# TD4-CORE.net
KiCad netlist of a schematic drawn in Altium Designer
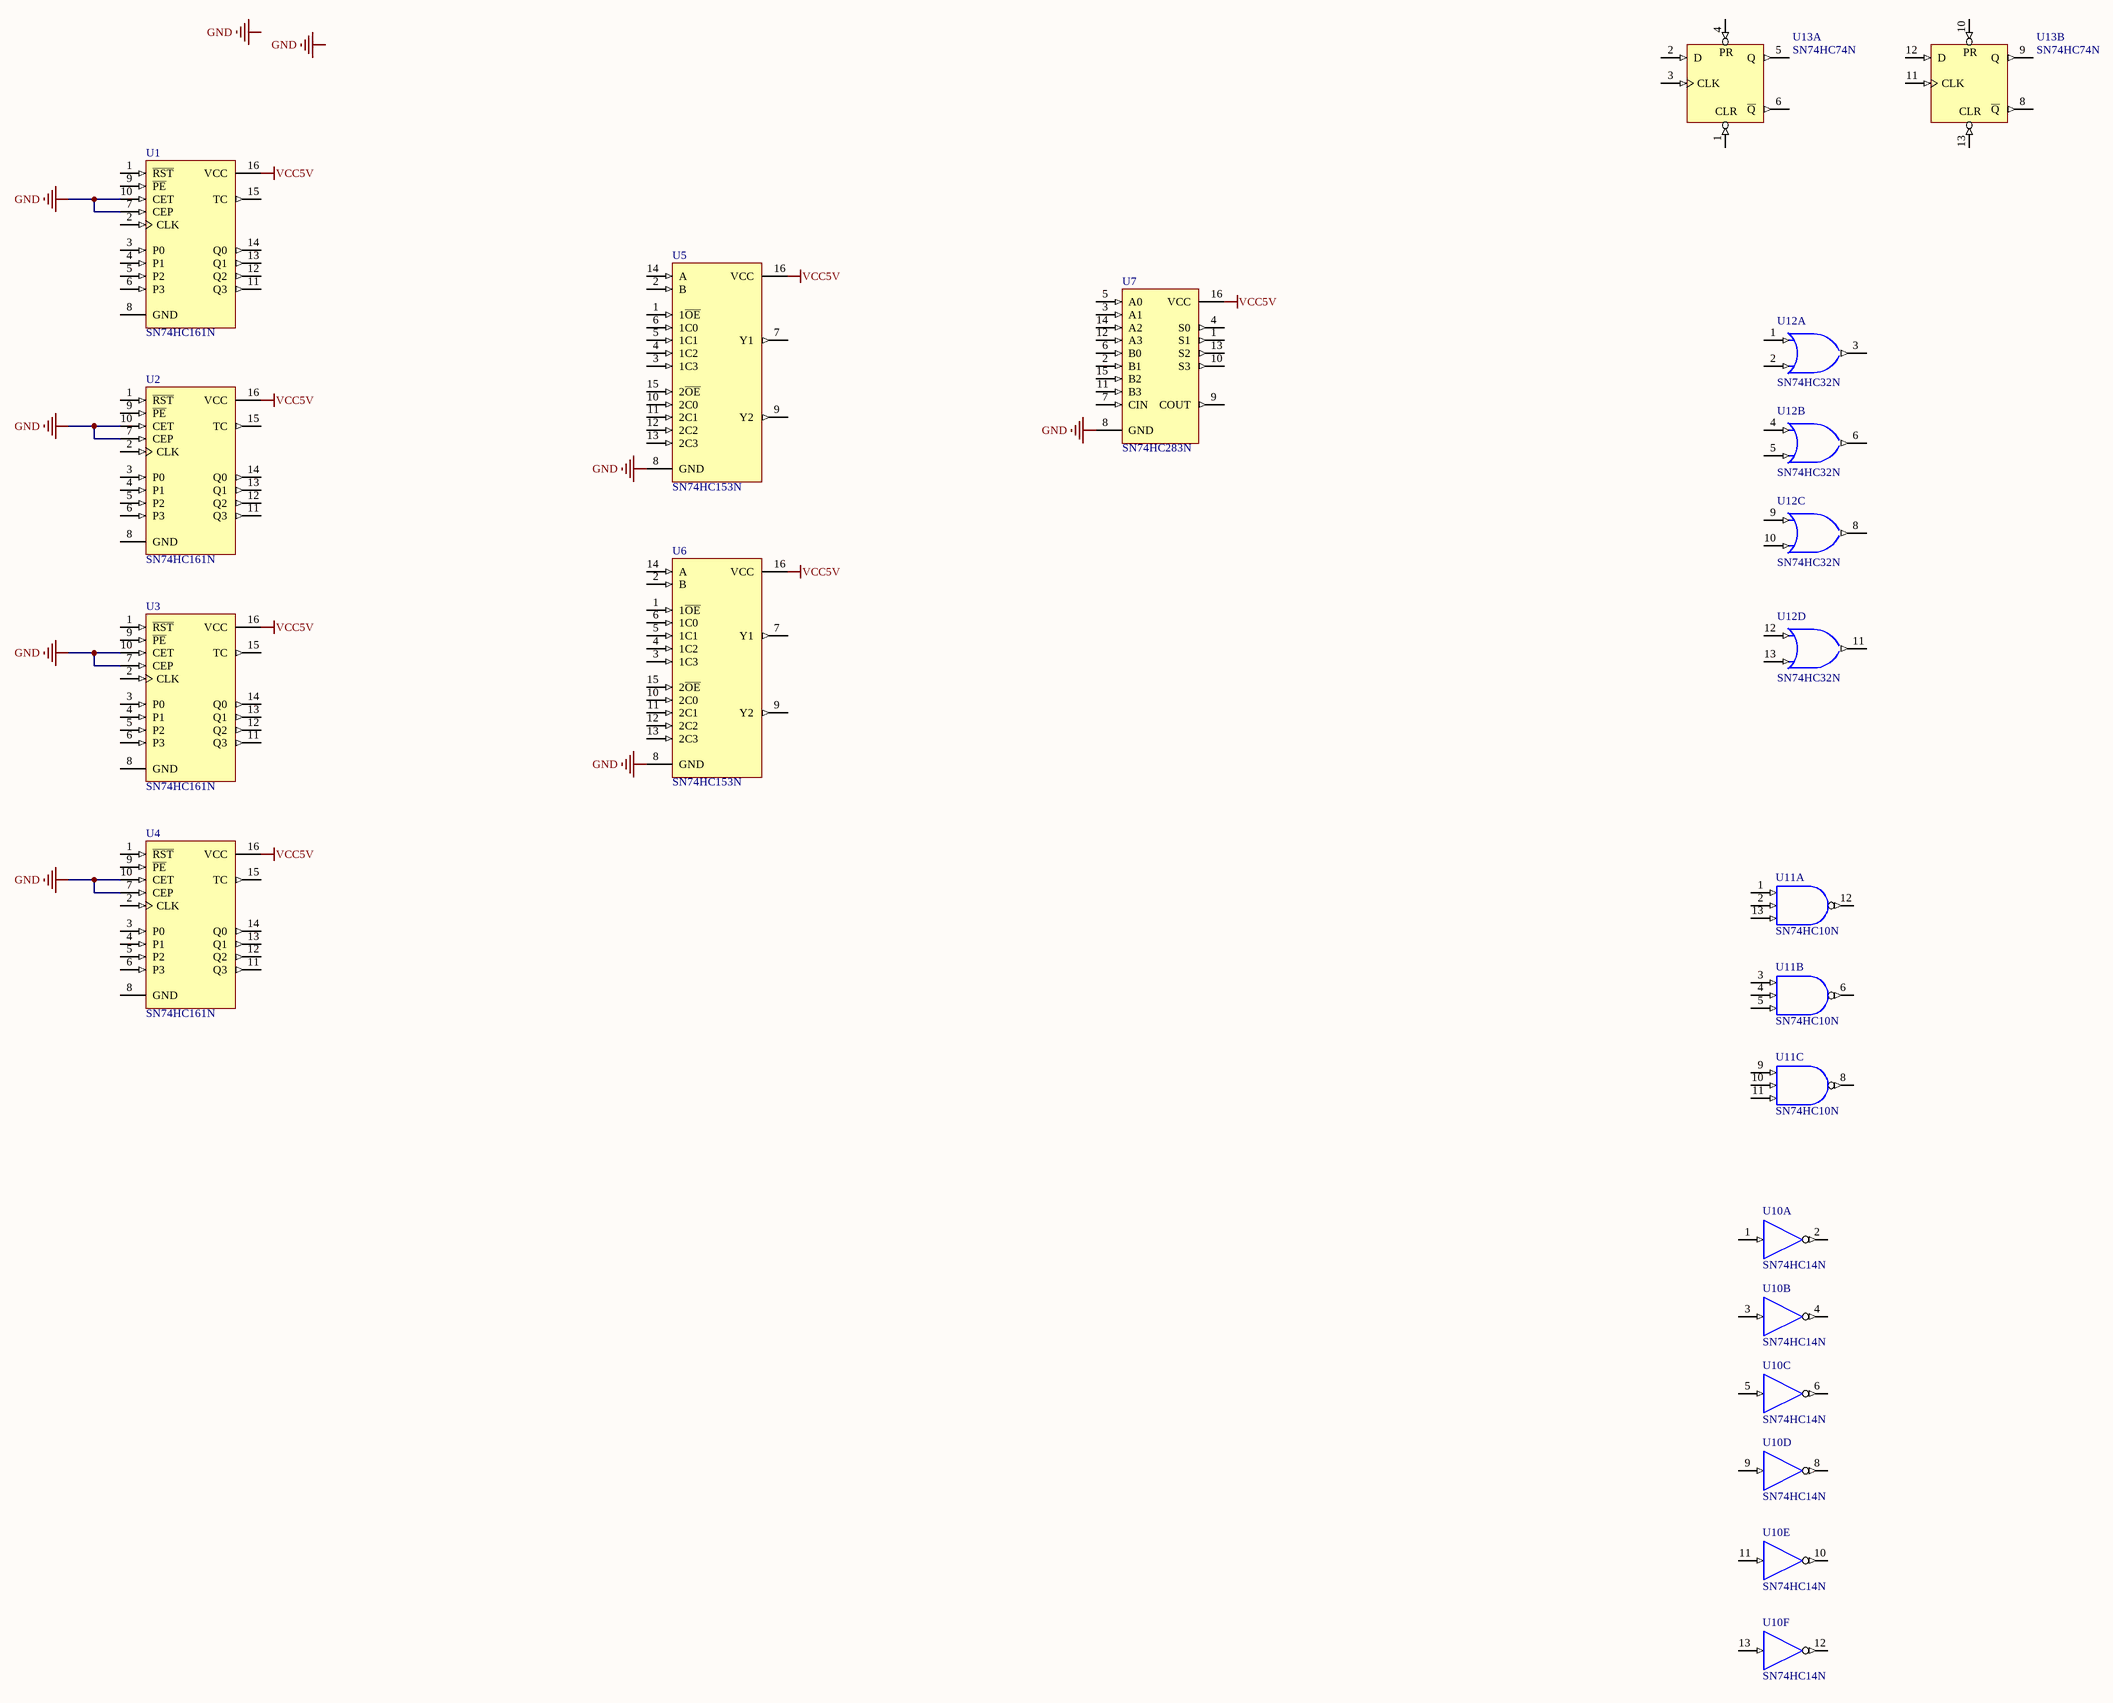
[diagram p0: TD4-CORE.SchDoc]

(export (version "E")
  (design (tool "Eeschema 10.0.6"))
  (components
    (comp (ref "U1")
      (value "SN74HC161N")
      (footprint "N016")
      (description "4-Bit Synchronous Binary Counter")
      (fields (field (name "PUBLISHER") "Altium Limited"))
      (libsource (lib "TI Logic Counter") (part "SN74HC161N"))
    )
    (comp (ref "U2")
      (value "SN74HC161N")
      (footprint "N016")
      (description "4-Bit Synchronous Binary Counter")
      (fields (field (name "PUBLISHER") "Altium Limited"))
      (libsource (lib "TI Logic Counter") (part "SN74HC161N"))
    )
    (comp (ref "U3")
      (value "SN74HC161N")
      (footprint "N016")
      (description "4-Bit Synchronous Binary Counter")
      (fields (field (name "PUBLISHER") "Altium Limited"))
      (libsource (lib "TI Logic Counter") (part "SN74HC161N"))
    )
    (comp (ref "U4")
      (value "SN74HC161N")
      (footprint "N016")
      (description "4-Bit Synchronous Binary Counter")
      (fields (field (name "PUBLISHER") "Altium Limited"))
      (libsource (lib "TI Logic Counter") (part "SN74HC161N"))
    )
    (comp (ref "U5")
      (value "SN74HC153N")
      (footprint "N016")
      (description "Dual 4-Line to 1-Line Data Selector/Multiplexer")
      (fields (field (name "PUBLISHER") "Altium Limited"))
      (libsource (lib "TI Logic Multiplexer") (part "SN74HC153N"))
    )
    (comp (ref "U6")
      (value "SN74HC153N")
      (footprint "N016")
      (description "Dual 4-Line to 1-Line Data Selector/Multiplexer")
      (fields (field (name "PUBLISHER") "Altium Limited"))
      (libsource (lib "TI Logic Multiplexer") (part "SN74HC153N"))
    )
    (comp (ref "U7")
      (value "SN74HC283N")
      (footprint "N016")
      (description "4-Bit Binary Full Adder with Fast Carry")
      (fields (field (name "PUBLISHER") "Altium Limited"))
      (libsource (lib "TI Logic Arithmetic") (part "SN74HC283N"))
    )
    (comp (ref "U10")
      (value "SN74HC14N")
      (footprint "N014")
      (description "Hex Schmitt-Trigger Inverter")
      (fields (field (name "PUBLISHER") "Altium Limited"))
      (libsource (lib "TI Logic Gate 2") (part "SN74HC14N"))
    )
    (comp (ref "U11")
      (value "SN74HC10N")
      (footprint "N014")
      (description "Triple 3-Input Positive-NAND Gate")
      (fields (field (name "PUBLISHER") "Altium Limited"))
      (libsource (lib "TI Logic Gate 2") (part "SN74HC10N"))
    )
    (comp (ref "U12")
      (value "SN74HC32N")
      (footprint "N014")
      (description "Quadruple 2-Input Positive-OR Gate")
      (fields (field (name "PUBLISHER") "Altium Limited"))
      (libsource (lib "TI Logic Gate 2") (part "SN74HC32N"))
    )
    (comp (ref "U13")
      (value "SN74HC74N")
      (footprint "N014")
      (description "Dual D-Type Positive-Edge-Triggered Flip-Flop with Clear and Preset")
      (fields (field (name "PUBLISHER") "Altium Limited"))
      (libsource (lib "TI Logic Flip-Flop") (part "SN74HC74N"))
    )
  )
  (nets
    (net (code "1") (name "GND") (class "Default")
      (node (ref "U1") (pin "10") (pinfunction "CET_10") (pintype "input"))
      (node (ref "U1") (pin "7") (pinfunction "CEP_7") (pintype "input"))
      (node (ref "U10") (pin "7") (pinfunction "GND_7") (pintype "power_in"))
      (node (ref "U11") (pin "7") (pinfunction "GND_7") (pintype "power_in"))
      (node (ref "U12") (pin "7") (pinfunction "GND_7") (pintype "power_in"))
      (node (ref "U13") (pin "7") (pinfunction "GND_7") (pintype "power_in"))
      (node (ref "U2") (pin "10") (pinfunction "CET_10") (pintype "input"))
      (node (ref "U2") (pin "7") (pinfunction "CEP_7") (pintype "input"))
      (node (ref "U3") (pin "10") (pinfunction "CET_10") (pintype "input"))
      (node (ref "U3") (pin "7") (pinfunction "CEP_7") (pintype "input"))
      (node (ref "U4") (pin "10") (pinfunction "CET_10") (pintype "input"))
      (node (ref "U4") (pin "7") (pinfunction "CEP_7") (pintype "input"))
      (node (ref "U5") (pin "8") (pinfunction "GND_8") (pintype "power_in"))
      (node (ref "U6") (pin "8") (pinfunction "GND_8") (pintype "power_in"))
      (node (ref "U7") (pin "8") (pinfunction "GND_8") (pintype "power_in"))
    )
    (net (code "2") (name "VCC") (class "Default")
      (node (ref "U10") (pin "14") (pinfunction "VCC_14") (pintype "power_in"))
      (node (ref "U11") (pin "14") (pinfunction "VCC_14") (pintype "power_in"))
      (node (ref "U12") (pin "14") (pinfunction "VCC_14") (pintype "power_in"))
      (node (ref "U13") (pin "14") (pinfunction "VCC_14") (pintype "power_in"))
    )
    (net (code "3") (name "VCC5V") (class "Default")
      (node (ref "U1") (pin "16") (pinfunction "VCC_16") (pintype "power_in"))
      (node (ref "U2") (pin "16") (pinfunction "VCC_16") (pintype "power_in"))
      (node (ref "U3") (pin "16") (pinfunction "VCC_16") (pintype "power_in"))
      (node (ref "U4") (pin "16") (pinfunction "VCC_16") (pintype "power_in"))
      (node (ref "U5") (pin "16") (pinfunction "VCC_16") (pintype "power_in"))
      (node (ref "U6") (pin "16") (pinfunction "VCC_16") (pintype "power_in"))
      (node (ref "U7") (pin "16") (pinfunction "VCC_16") (pintype "power_in"))
    )
    (net (code "4") (name "unconnected-(U1-CLK-Pad2)") (class "Default")
      (node (ref "U1") (pin "2") (pinfunction "CLK_2") (pintype "input"))
    )
    (net (code "5") (name "unconnected-(U1-GND-Pad8)") (class "Default")
      (node (ref "U1") (pin "8") (pinfunction "GND_8") (pintype "power_in"))
    )
    (net (code "6") (name "unconnected-(U1-P0-Pad3)") (class "Default")
      (node (ref "U1") (pin "3") (pinfunction "P0_3") (pintype "input"))
    )
    (net (code "7") (name "unconnected-(U1-P1-Pad4)") (class "Default")
      (node (ref "U1") (pin "4") (pinfunction "P1_4") (pintype "input"))
    )
    (net (code "8") (name "unconnected-(U1-P2-Pad5)") (class "Default")
      (node (ref "U1") (pin "5") (pinfunction "P2_5") (pintype "input"))
    )
    (net (code "9") (name "unconnected-(U1-P3-Pad6)") (class "Default")
      (node (ref "U1") (pin "6") (pinfunction "P3_6") (pintype "input"))
    )
    (net (code "10") (name "unconnected-(U1-Q0-Pad14)") (class "Default")
      (node (ref "U1") (pin "14") (pinfunction "Q0_14") (pintype "output"))
    )
    (net (code "11") (name "unconnected-(U1-Q1-Pad13)") (class "Default")
      (node (ref "U1") (pin "13") (pinfunction "Q1_13") (pintype "output"))
    )
    (net (code "12") (name "unconnected-(U1-Q2-Pad12)") (class "Default")
      (node (ref "U1") (pin "12") (pinfunction "Q2_12") (pintype "output"))
    )
    (net (code "13") (name "unconnected-(U1-Q3-Pad11)") (class "Default")
      (node (ref "U1") (pin "11") (pinfunction "Q3_11") (pintype "output"))
    )
    (net (code "14") (name "unconnected-(U1-TC-Pad15)") (class "Default")
      (node (ref "U1") (pin "15") (pinfunction "TC_15") (pintype "output"))
    )
    (net (code "15") (name "unconnected-(U1-~{PE}-Pad9)") (class "Default")
      (node (ref "U1") (pin "9") (pinfunction "~{PE}_9") (pintype "input"))
    )
    (net (code "16") (name "unconnected-(U1-~{RST}-Pad1)") (class "Default")
      (node (ref "U1") (pin "1") (pinfunction "~{RST}_1") (pintype "input"))
    )
    (net (code "17") (name "unconnected-(U2-CLK-Pad2)") (class "Default")
      (node (ref "U2") (pin "2") (pinfunction "CLK_2") (pintype "input"))
    )
    (net (code "18") (name "unconnected-(U2-GND-Pad8)") (class "Default")
      (node (ref "U2") (pin "8") (pinfunction "GND_8") (pintype "power_in"))
    )
    (net (code "19") (name "unconnected-(U2-P0-Pad3)") (class "Default")
      (node (ref "U2") (pin "3") (pinfunction "P0_3") (pintype "input"))
    )
    (net (code "20") (name "unconnected-(U2-P1-Pad4)") (class "Default")
      (node (ref "U2") (pin "4") (pinfunction "P1_4") (pintype "input"))
    )
    (net (code "21") (name "unconnected-(U2-P2-Pad5)") (class "Default")
      (node (ref "U2") (pin "5") (pinfunction "P2_5") (pintype "input"))
    )
    (net (code "22") (name "unconnected-(U2-P3-Pad6)") (class "Default")
      (node (ref "U2") (pin "6") (pinfunction "P3_6") (pintype "input"))
    )
    (net (code "23") (name "unconnected-(U2-Q0-Pad14)") (class "Default")
      (node (ref "U2") (pin "14") (pinfunction "Q0_14") (pintype "output"))
    )
    (net (code "24") (name "unconnected-(U2-Q1-Pad13)") (class "Default")
      (node (ref "U2") (pin "13") (pinfunction "Q1_13") (pintype "output"))
    )
    (net (code "25") (name "unconnected-(U2-Q2-Pad12)") (class "Default")
      (node (ref "U2") (pin "12") (pinfunction "Q2_12") (pintype "output"))
    )
    (net (code "26") (name "unconnected-(U2-Q3-Pad11)") (class "Default")
      (node (ref "U2") (pin "11") (pinfunction "Q3_11") (pintype "output"))
    )
    (net (code "27") (name "unconnected-(U2-TC-Pad15)") (class "Default")
      (node (ref "U2") (pin "15") (pinfunction "TC_15") (pintype "output"))
    )
    (net (code "28") (name "unconnected-(U2-~{PE}-Pad9)") (class "Default")
      (node (ref "U2") (pin "9") (pinfunction "~{PE}_9") (pintype "input"))
    )
    (net (code "29") (name "unconnected-(U2-~{RST}-Pad1)") (class "Default")
      (node (ref "U2") (pin "1") (pinfunction "~{RST}_1") (pintype "input"))
    )
    (net (code "30") (name "unconnected-(U3-CLK-Pad2)") (class "Default")
      (node (ref "U3") (pin "2") (pinfunction "CLK_2") (pintype "input"))
    )
    (net (code "31") (name "unconnected-(U3-GND-Pad8)") (class "Default")
      (node (ref "U3") (pin "8") (pinfunction "GND_8") (pintype "power_in"))
    )
    (net (code "32") (name "unconnected-(U3-P0-Pad3)") (class "Default")
      (node (ref "U3") (pin "3") (pinfunction "P0_3") (pintype "input"))
    )
    (net (code "33") (name "unconnected-(U3-P1-Pad4)") (class "Default")
      (node (ref "U3") (pin "4") (pinfunction "P1_4") (pintype "input"))
    )
    (net (code "34") (name "unconnected-(U3-P2-Pad5)") (class "Default")
      (node (ref "U3") (pin "5") (pinfunction "P2_5") (pintype "input"))
    )
    (net (code "35") (name "unconnected-(U3-P3-Pad6)") (class "Default")
      (node (ref "U3") (pin "6") (pinfunction "P3_6") (pintype "input"))
    )
    (net (code "36") (name "unconnected-(U3-Q0-Pad14)") (class "Default")
      (node (ref "U3") (pin "14") (pinfunction "Q0_14") (pintype "output"))
    )
    (net (code "37") (name "unconnected-(U3-Q1-Pad13)") (class "Default")
      (node (ref "U3") (pin "13") (pinfunction "Q1_13") (pintype "output"))
    )
    (net (code "38") (name "unconnected-(U3-Q2-Pad12)") (class "Default")
      (node (ref "U3") (pin "12") (pinfunction "Q2_12") (pintype "output"))
    )
    (net (code "39") (name "unconnected-(U3-Q3-Pad11)") (class "Default")
      (node (ref "U3") (pin "11") (pinfunction "Q3_11") (pintype "output"))
    )
    (net (code "40") (name "unconnected-(U3-TC-Pad15)") (class "Default")
      (node (ref "U3") (pin "15") (pinfunction "TC_15") (pintype "output"))
    )
    (net (code "41") (name "unconnected-(U3-~{PE}-Pad9)") (class "Default")
      (node (ref "U3") (pin "9") (pinfunction "~{PE}_9") (pintype "input"))
    )
    (net (code "42") (name "unconnected-(U3-~{RST}-Pad1)") (class "Default")
      (node (ref "U3") (pin "1") (pinfunction "~{RST}_1") (pintype "input"))
    )
    (net (code "43") (name "unconnected-(U4-CLK-Pad2)") (class "Default")
      (node (ref "U4") (pin "2") (pinfunction "CLK_2") (pintype "input"))
    )
    (net (code "44") (name "unconnected-(U4-GND-Pad8)") (class "Default")
      (node (ref "U4") (pin "8") (pinfunction "GND_8") (pintype "power_in"))
    )
    (net (code "45") (name "unconnected-(U4-P0-Pad3)") (class "Default")
      (node (ref "U4") (pin "3") (pinfunction "P0_3") (pintype "input"))
    )
    (net (code "46") (name "unconnected-(U4-P1-Pad4)") (class "Default")
      (node (ref "U4") (pin "4") (pinfunction "P1_4") (pintype "input"))
    )
    (net (code "47") (name "unconnected-(U4-P2-Pad5)") (class "Default")
      (node (ref "U4") (pin "5") (pinfunction "P2_5") (pintype "input"))
    )
    (net (code "48") (name "unconnected-(U4-P3-Pad6)") (class "Default")
      (node (ref "U4") (pin "6") (pinfunction "P3_6") (pintype "input"))
    )
    (net (code "49") (name "unconnected-(U4-Q0-Pad14)") (class "Default")
      (node (ref "U4") (pin "14") (pinfunction "Q0_14") (pintype "output"))
    )
    (net (code "50") (name "unconnected-(U4-Q1-Pad13)") (class "Default")
      (node (ref "U4") (pin "13") (pinfunction "Q1_13") (pintype "output"))
    )
    (net (code "51") (name "unconnected-(U4-Q2-Pad12)") (class "Default")
      (node (ref "U4") (pin "12") (pinfunction "Q2_12") (pintype "output"))
    )
    (net (code "52") (name "unconnected-(U4-Q3-Pad11)") (class "Default")
      (node (ref "U4") (pin "11") (pinfunction "Q3_11") (pintype "output"))
    )
    (net (code "53") (name "unconnected-(U4-TC-Pad15)") (class "Default")
      (node (ref "U4") (pin "15") (pinfunction "TC_15") (pintype "output"))
    )
    (net (code "54") (name "unconnected-(U4-~{PE}-Pad9)") (class "Default")
      (node (ref "U4") (pin "9") (pinfunction "~{PE}_9") (pintype "input"))
    )
    (net (code "55") (name "unconnected-(U4-~{RST}-Pad1)") (class "Default")
      (node (ref "U4") (pin "1") (pinfunction "~{RST}_1") (pintype "input"))
    )
    (net (code "56") (name "unconnected-(U5-1C0-Pad6)") (class "Default")
      (node (ref "U5") (pin "6") (pinfunction "1C0_6") (pintype "input"))
    )
    (net (code "57") (name "unconnected-(U5-1C1-Pad5)") (class "Default")
      (node (ref "U5") (pin "5") (pinfunction "1C1_5") (pintype "input"))
    )
    (net (code "58") (name "unconnected-(U5-1C2-Pad4)") (class "Default")
      (node (ref "U5") (pin "4") (pinfunction "1C2_4") (pintype "input"))
    )
    (net (code "59") (name "unconnected-(U5-1C3-Pad3)") (class "Default")
      (node (ref "U5") (pin "3") (pinfunction "1C3_3") (pintype "input"))
    )
    (net (code "60") (name "unconnected-(U5-1~{OE}-Pad1)") (class "Default")
      (node (ref "U5") (pin "1") (pinfunction "1~{OE}_1") (pintype "input"))
    )
    (net (code "61") (name "unconnected-(U5-2C0-Pad10)") (class "Default")
      (node (ref "U5") (pin "10") (pinfunction "2C0_10") (pintype "input"))
    )
    (net (code "62") (name "unconnected-(U5-2C1-Pad11)") (class "Default")
      (node (ref "U5") (pin "11") (pinfunction "2C1_11") (pintype "input"))
    )
    (net (code "63") (name "unconnected-(U5-2C2-Pad12)") (class "Default")
      (node (ref "U5") (pin "12") (pinfunction "2C2_12") (pintype "input"))
    )
    (net (code "64") (name "unconnected-(U5-2C3-Pad13)") (class "Default")
      (node (ref "U5") (pin "13") (pinfunction "2C3_13") (pintype "input"))
    )
    (net (code "65") (name "unconnected-(U5-2~{OE}-Pad15)") (class "Default")
      (node (ref "U5") (pin "15") (pinfunction "2~{OE}_15") (pintype "input"))
    )
    (net (code "66") (name "unconnected-(U5-A-Pad14)") (class "Default")
      (node (ref "U5") (pin "14") (pinfunction "A_14") (pintype "input"))
    )
    (net (code "67") (name "unconnected-(U5-B-Pad2)") (class "Default")
      (node (ref "U5") (pin "2") (pinfunction "B_2") (pintype "input"))
    )
    (net (code "68") (name "unconnected-(U5-Y1-Pad7)") (class "Default")
      (node (ref "U5") (pin "7") (pinfunction "Y1_7") (pintype "output"))
    )
    (net (code "69") (name "unconnected-(U5-Y2-Pad9)") (class "Default")
      (node (ref "U5") (pin "9") (pinfunction "Y2_9") (pintype "output"))
    )
    (net (code "70") (name "unconnected-(U6-1C0-Pad6)") (class "Default")
      (node (ref "U6") (pin "6") (pinfunction "1C0_6") (pintype "input"))
    )
    (net (code "71") (name "unconnected-(U6-1C1-Pad5)") (class "Default")
      (node (ref "U6") (pin "5") (pinfunction "1C1_5") (pintype "input"))
    )
    (net (code "72") (name "unconnected-(U6-1C2-Pad4)") (class "Default")
      (node (ref "U6") (pin "4") (pinfunction "1C2_4") (pintype "input"))
    )
    (net (code "73") (name "unconnected-(U6-1C3-Pad3)") (class "Default")
      (node (ref "U6") (pin "3") (pinfunction "1C3_3") (pintype "input"))
    )
    (net (code "74") (name "unconnected-(U6-1~{OE}-Pad1)") (class "Default")
      (node (ref "U6") (pin "1") (pinfunction "1~{OE}_1") (pintype "input"))
    )
    (net (code "75") (name "unconnected-(U6-2C0-Pad10)") (class "Default")
      (node (ref "U6") (pin "10") (pinfunction "2C0_10") (pintype "input"))
    )
    (net (code "76") (name "unconnected-(U6-2C1-Pad11)") (class "Default")
      (node (ref "U6") (pin "11") (pinfunction "2C1_11") (pintype "input"))
    )
    (net (code "77") (name "unconnected-(U6-2C2-Pad12)") (class "Default")
      (node (ref "U6") (pin "12") (pinfunction "2C2_12") (pintype "input"))
    )
    (net (code "78") (name "unconnected-(U6-2C3-Pad13)") (class "Default")
      (node (ref "U6") (pin "13") (pinfunction "2C3_13") (pintype "input"))
    )
    (net (code "79") (name "unconnected-(U6-2~{OE}-Pad15)") (class "Default")
      (node (ref "U6") (pin "15") (pinfunction "2~{OE}_15") (pintype "input"))
    )
    (net (code "80") (name "unconnected-(U6-A-Pad14)") (class "Default")
      (node (ref "U6") (pin "14") (pinfunction "A_14") (pintype "input"))
    )
    (net (code "81") (name "unconnected-(U6-B-Pad2)") (class "Default")
      (node (ref "U6") (pin "2") (pinfunction "B_2") (pintype "input"))
    )
    (net (code "82") (name "unconnected-(U6-Y1-Pad7)") (class "Default")
      (node (ref "U6") (pin "7") (pinfunction "Y1_7") (pintype "output"))
    )
    (net (code "83") (name "unconnected-(U6-Y2-Pad9)") (class "Default")
      (node (ref "U6") (pin "9") (pinfunction "Y2_9") (pintype "output"))
    )
    (net (code "84") (name "unconnected-(U7-A0-Pad5)") (class "Default")
      (node (ref "U7") (pin "5") (pinfunction "A0_5") (pintype "input"))
    )
    (net (code "85") (name "unconnected-(U7-A1-Pad3)") (class "Default")
      (node (ref "U7") (pin "3") (pinfunction "A1_3") (pintype "input"))
    )
    (net (code "86") (name "unconnected-(U7-A2-Pad14)") (class "Default")
      (node (ref "U7") (pin "14") (pinfunction "A2_14") (pintype "input"))
    )
    (net (code "87") (name "unconnected-(U7-A3-Pad12)") (class "Default")
      (node (ref "U7") (pin "12") (pinfunction "A3_12") (pintype "input"))
    )
    (net (code "88") (name "unconnected-(U7-B0-Pad6)") (class "Default")
      (node (ref "U7") (pin "6") (pinfunction "B0_6") (pintype "input"))
    )
    (net (code "89") (name "unconnected-(U7-B1-Pad2)") (class "Default")
      (node (ref "U7") (pin "2") (pinfunction "B1_2") (pintype "input"))
    )
    (net (code "90") (name "unconnected-(U7-B2-Pad15)") (class "Default")
      (node (ref "U7") (pin "15") (pinfunction "B2_15") (pintype "input"))
    )
    (net (code "91") (name "unconnected-(U7-B3-Pad11)") (class "Default")
      (node (ref "U7") (pin "11") (pinfunction "B3_11") (pintype "input"))
    )
    (net (code "92") (name "unconnected-(U7-CIN-Pad7)") (class "Default")
      (node (ref "U7") (pin "7") (pinfunction "CIN_7") (pintype "input"))
    )
    (net (code "93") (name "unconnected-(U7-COUT-Pad9)") (class "Default")
      (node (ref "U7") (pin "9") (pinfunction "COUT_9") (pintype "output"))
    )
    (net (code "94") (name "unconnected-(U7-S0-Pad4)") (class "Default")
      (node (ref "U7") (pin "4") (pinfunction "S0_4") (pintype "output"))
    )
    (net (code "95") (name "unconnected-(U7-S1-Pad1)") (class "Default")
      (node (ref "U7") (pin "1") (pinfunction "S1_1") (pintype "output"))
    )
    (net (code "96") (name "unconnected-(U7-S2-Pad13)") (class "Default")
      (node (ref "U7") (pin "13") (pinfunction "S2_13") (pintype "output"))
    )
    (net (code "97") (name "unconnected-(U7-S3-Pad10)") (class "Default")
      (node (ref "U7") (pin "10") (pinfunction "S3_10") (pintype "output"))
    )
    (net (code "98") (name "unconnected-(U10A-A-Pad1)") (class "Default")
      (node (ref "U10") (pin "1") (pinfunction "A_1") (pintype "input"))
    )
    (net (code "99") (name "unconnected-(U10A-Y-Pad2)") (class "Default")
      (node (ref "U10") (pin "2") (pinfunction "Y_2") (pintype "output"))
    )
    (net (code "100") (name "unconnected-(U10B-A-Pad3)") (class "Default")
      (node (ref "U10") (pin "3") (pinfunction "A_3") (pintype "input"))
    )
    (net (code "101") (name "unconnected-(U10B-Y-Pad4)") (class "Default")
      (node (ref "U10") (pin "4") (pinfunction "Y_4") (pintype "output"))
    )
    (net (code "102") (name "unconnected-(U10C-A-Pad5)") (class "Default")
      (node (ref "U10") (pin "5") (pinfunction "A_5") (pintype "input"))
    )
    (net (code "103") (name "unconnected-(U10C-Y-Pad6)") (class "Default")
      (node (ref "U10") (pin "6") (pinfunction "Y_6") (pintype "output"))
    )
    (net (code "104") (name "unconnected-(U10D-A-Pad9)") (class "Default")
      (node (ref "U10") (pin "9") (pinfunction "A_9") (pintype "input"))
    )
    (net (code "105") (name "unconnected-(U10D-Y-Pad8)") (class "Default")
      (node (ref "U10") (pin "8") (pinfunction "Y_8") (pintype "output"))
    )
    (net (code "106") (name "unconnected-(U10E-A-Pad11)") (class "Default")
      (node (ref "U10") (pin "11") (pinfunction "A_11") (pintype "input"))
    )
    (net (code "107") (name "unconnected-(U10E-Y-Pad10)") (class "Default")
      (node (ref "U10") (pin "10") (pinfunction "Y_10") (pintype "output"))
    )
    (net (code "108") (name "unconnected-(U10F-A-Pad13)") (class "Default")
      (node (ref "U10") (pin "13") (pinfunction "A_13") (pintype "input"))
    )
    (net (code "109") (name "unconnected-(U10F-Y-Pad12)") (class "Default")
      (node (ref "U10") (pin "12") (pinfunction "Y_12") (pintype "output"))
    )
    (net (code "110") (name "unconnected-(U11A-A-Pad1)") (class "Default")
      (node (ref "U11") (pin "1") (pinfunction "A_1") (pintype "input"))
    )
    (net (code "111") (name "unconnected-(U11A-B-Pad2)") (class "Default")
      (node (ref "U11") (pin "2") (pinfunction "B_2") (pintype "input"))
    )
    (net (code "112") (name "unconnected-(U11A-C-Pad13)") (class "Default")
      (node (ref "U11") (pin "13") (pinfunction "C_13") (pintype "input"))
    )
    (net (code "113") (name "unconnected-(U11A-Y-Pad12)") (class "Default")
      (node (ref "U11") (pin "12") (pinfunction "Y_12") (pintype "output"))
    )
    (net (code "114") (name "unconnected-(U11B-A-Pad3)") (class "Default")
      (node (ref "U11") (pin "3") (pinfunction "A_3") (pintype "input"))
    )
    (net (code "115") (name "unconnected-(U11B-B-Pad4)") (class "Default")
      (node (ref "U11") (pin "4") (pinfunction "B_4") (pintype "input"))
    )
    (net (code "116") (name "unconnected-(U11B-C-Pad5)") (class "Default")
      (node (ref "U11") (pin "5") (pinfunction "C_5") (pintype "input"))
    )
    (net (code "117") (name "unconnected-(U11B-Y-Pad6)") (class "Default")
      (node (ref "U11") (pin "6") (pinfunction "Y_6") (pintype "output"))
    )
    (net (code "118") (name "unconnected-(U11C-A-Pad9)") (class "Default")
      (node (ref "U11") (pin "9") (pinfunction "A_9") (pintype "input"))
    )
    (net (code "119") (name "unconnected-(U11C-B-Pad10)") (class "Default")
      (node (ref "U11") (pin "10") (pinfunction "B_10") (pintype "input"))
    )
    (net (code "120") (name "unconnected-(U11C-C-Pad11)") (class "Default")
      (node (ref "U11") (pin "11") (pinfunction "C_11") (pintype "input"))
    )
    (net (code "121") (name "unconnected-(U11C-Y-Pad8)") (class "Default")
      (node (ref "U11") (pin "8") (pinfunction "Y_8") (pintype "output"))
    )
    (net (code "122") (name "unconnected-(U12A-A-Pad1)") (class "Default")
      (node (ref "U12") (pin "1") (pinfunction "A_1") (pintype "input"))
    )
    (net (code "123") (name "unconnected-(U12A-B-Pad2)") (class "Default")
      (node (ref "U12") (pin "2") (pinfunction "B_2") (pintype "input"))
    )
    (net (code "124") (name "unconnected-(U12A-Y-Pad3)") (class "Default")
      (node (ref "U12") (pin "3") (pinfunction "Y_3") (pintype "output"))
    )
    (net (code "125") (name "unconnected-(U12B-A-Pad4)") (class "Default")
      (node (ref "U12") (pin "4") (pinfunction "A_4") (pintype "input"))
    )
    (net (code "126") (name "unconnected-(U12B-B-Pad5)") (class "Default")
      (node (ref "U12") (pin "5") (pinfunction "B_5") (pintype "input"))
    )
    (net (code "127") (name "unconnected-(U12B-Y-Pad6)") (class "Default")
      (node (ref "U12") (pin "6") (pinfunction "Y_6") (pintype "output"))
    )
    (net (code "128") (name "unconnected-(U12C-A-Pad9)") (class "Default")
      (node (ref "U12") (pin "9") (pinfunction "A_9") (pintype "input"))
    )
    (net (code "129") (name "unconnected-(U12C-B-Pad10)") (class "Default")
      (node (ref "U12") (pin "10") (pinfunction "B_10") (pintype "input"))
    )
    (net (code "130") (name "unconnected-(U12C-Y-Pad8)") (class "Default")
      (node (ref "U12") (pin "8") (pinfunction "Y_8") (pintype "output"))
    )
    (net (code "131") (name "unconnected-(U12D-A-Pad12)") (class "Default")
      (node (ref "U12") (pin "12") (pinfunction "A_12") (pintype "input"))
    )
    (net (code "132") (name "unconnected-(U12D-B-Pad13)") (class "Default")
      (node (ref "U12") (pin "13") (pinfunction "B_13") (pintype "input"))
    )
    (net (code "133") (name "unconnected-(U12D-Y-Pad11)") (class "Default")
      (node (ref "U12") (pin "11") (pinfunction "Y_11") (pintype "output"))
    )
    (net (code "134") (name "unconnected-(U13A-CLK-Pad3)") (class "Default")
      (node (ref "U13") (pin "3") (pinfunction "CLK_3") (pintype "input"))
    )
    (net (code "135") (name "unconnected-(U13A-CLR-Pad1)") (class "Default")
      (node (ref "U13") (pin "1") (pinfunction "CLR_1") (pintype "input"))
    )
    (net (code "136") (name "unconnected-(U13A-D-Pad2)") (class "Default")
      (node (ref "U13") (pin "2") (pinfunction "D_2") (pintype "input"))
    )
    (net (code "137") (name "unconnected-(U13A-PR-Pad4)") (class "Default")
      (node (ref "U13") (pin "4") (pinfunction "PR_4") (pintype "input"))
    )
    (net (code "138") (name "unconnected-(U13A-Q-Pad5)") (class "Default")
      (node (ref "U13") (pin "5") (pinfunction "Q_5") (pintype "output"))
    )
    (net (code "139") (name "unconnected-(U13A-~{Q}-Pad6)") (class "Default")
      (node (ref "U13") (pin "6") (pinfunction "~{Q}_6") (pintype "output"))
    )
    (net (code "140") (name "unconnected-(U13B-CLK-Pad11)") (class "Default")
      (node (ref "U13") (pin "11") (pinfunction "CLK_11") (pintype "input"))
    )
    (net (code "141") (name "unconnected-(U13B-CLR-Pad13)") (class "Default")
      (node (ref "U13") (pin "13") (pinfunction "CLR_13") (pintype "input"))
    )
    (net (code "142") (name "unconnected-(U13B-D-Pad12)") (class "Default")
      (node (ref "U13") (pin "12") (pinfunction "D_12") (pintype "input"))
    )
    (net (code "143") (name "unconnected-(U13B-PR-Pad10)") (class "Default")
      (node (ref "U13") (pin "10") (pinfunction "PR_10") (pintype "input"))
    )
    (net (code "144") (name "unconnected-(U13B-Q-Pad9)") (class "Default")
      (node (ref "U13") (pin "9") (pinfunction "Q_9") (pintype "output"))
    )
    (net (code "145") (name "unconnected-(U13B-~{Q}-Pad8)") (class "Default")
      (node (ref "U13") (pin "8") (pinfunction "~{Q}_8") (pintype "output"))
    )
  )
)
